# ESP8266-07.net
KiCad netlist of a schematic drawn in EAGLE
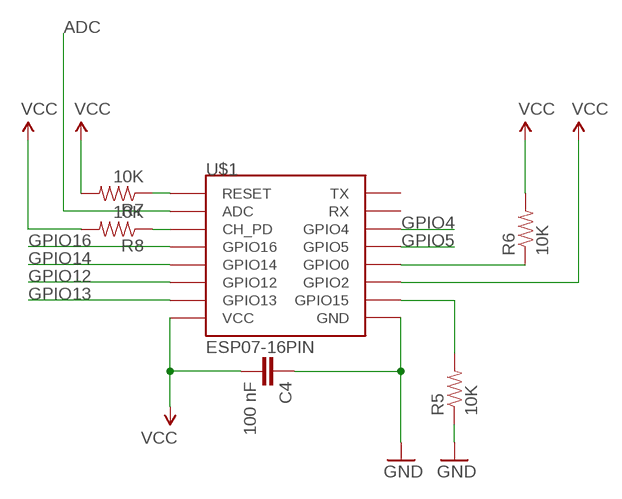
[diagram p0: schematic, sheet 1]

(export (version "E")
  (design (tool "Eeschema 10.0.6"))
  (components
    (comp (ref "C4")
      (value "100 nF")
      (footprint "eagle-import:0805")
      (libsource (lib "eagle-import") (part "CAP0805"))
    )
    (comp (ref "R5")
      (value "10K")
      (footprint "eagle-import:0805")
      (libsource (lib "eagle-import") (part "RESISTOR0805-RES"))
    )
    (comp (ref "R6")
      (value "10K")
      (footprint "eagle-import:0805")
      (libsource (lib "eagle-import") (part "RESISTOR0805-RES"))
    )
    (comp (ref "R7")
      (value "10K")
      (footprint "eagle-import:0805")
      (libsource (lib "eagle-import") (part "RESISTOR0805-RES"))
    )
    (comp (ref "R8")
      (value "10K")
      (footprint "eagle-import:0805")
      (libsource (lib "eagle-import") (part "RESISTOR0805-RES"))
    )
    (comp (ref "U$1")
      (value "ESP07-16PIN")
      (footprint "eagle-import:ESP07-16PIN")
      (libsource (lib "eagle-import") (part "ESP07-16PIN"))
    )
  )
  (nets
    (net (code "1") (name "/ADC") (class "Default")
      (node (ref "U$1") (pin "ADC") (pinfunction "ADC_ADC") (pintype "bidirectional"))
    )
    (net (code "2") (name "/GPIO4") (class "Default")
      (node (ref "U$1") (pin "GPIO4") (pinfunction "GPIO4_GPIO4") (pintype "bidirectional"))
    )
    (net (code "3") (name "/GPIO5") (class "Default")
      (node (ref "U$1") (pin "GPIO5") (pinfunction "GPIO5_GPIO5") (pintype "bidirectional"))
    )
    (net (code "4") (name "/GPIO12") (class "Default")
      (node (ref "U$1") (pin "GPIO12") (pinfunction "GPIO12_GPIO12") (pintype "bidirectional"))
    )
    (net (code "5") (name "/GPIO13") (class "Default")
      (node (ref "U$1") (pin "GPIO13") (pinfunction "GPIO13_GPIO13") (pintype "bidirectional"))
    )
    (net (code "6") (name "/GPIO14") (class "Default")
      (node (ref "U$1") (pin "GPIO14") (pinfunction "GPIO14_GPIO14") (pintype "bidirectional"))
    )
    (net (code "7") (name "/GPIO16") (class "Default")
      (node (ref "U$1") (pin "GPIO16") (pinfunction "GPIO16_GPIO16") (pintype "bidirectional"))
    )
    (net (code "8") (name "GND") (class "Default")
      (node (ref "C4") (pin "1") (pinfunction "1_1") (pintype "passive"))
      (node (ref "R5") (pin "1") (pinfunction "1_1") (pintype "passive"))
      (node (ref "U$1") (pin "GND") (pinfunction "GND_GND") (pintype "bidirectional"))
    )
    (net (code "9") (name "Net-(R5-Pad2)") (class "Default")
      (node (ref "R5") (pin "2") (pinfunction "2_2") (pintype "passive"))
      (node (ref "U$1") (pin "GPIO15") (pinfunction "GPIO15_GPIO15") (pintype "bidirectional"))
    )
    (net (code "10") (name "Net-(R6-Pad1)") (class "Default")
      (node (ref "R6") (pin "1") (pinfunction "1_1") (pintype "passive"))
      (node (ref "U$1") (pin "GPIO0") (pinfunction "GPIO0_GPIO0") (pintype "bidirectional"))
    )
    (net (code "11") (name "Net-(R8-Pad1)") (class "Default")
      (node (ref "R8") (pin "1") (pinfunction "1_1") (pintype "passive"))
      (node (ref "U$1") (pin "CH_PD") (pinfunction "CH_PD_CH_PD") (pintype "bidirectional"))
    )
    (net (code "12") (name "Net-(U$1-RESET)") (class "Default")
      (node (ref "R7") (pin "1") (pinfunction "1_1") (pintype "passive"))
      (node (ref "U$1") (pin "REST") (pinfunction "RESET_REST") (pintype "bidirectional"))
    )
    (net (code "13") (name "VCC") (class "Default")
      (node (ref "C4") (pin "2") (pinfunction "2_2") (pintype "passive"))
      (node (ref "R6") (pin "2") (pinfunction "2_2") (pintype "passive"))
      (node (ref "R7") (pin "2") (pinfunction "2_2") (pintype "passive"))
      (node (ref "R8") (pin "2") (pinfunction "2_2") (pintype "passive"))
      (node (ref "U$1") (pin "GPIO2") (pinfunction "GPIO2_GPIO2") (pintype "bidirectional"))
      (node (ref "U$1") (pin "VCC") (pinfunction "VCC_VCC") (pintype "bidirectional"))
    )
    (net (code "14") (name "unconnected-(U$1-PadRX)") (class "Default")
      (node (ref "U$1") (pin "RX") (pinfunction "RX_RX") (pintype "bidirectional"))
    )
    (net (code "15") (name "unconnected-(U$1-PadTX)") (class "Default")
      (node (ref "U$1") (pin "TX") (pinfunction "TX_TX") (pintype "bidirectional"))
    )
  )
)
